# MorseCodeExternalMicCircuit_Eagle_schema.net
KiCad netlist of a schematic drawn in EAGLE
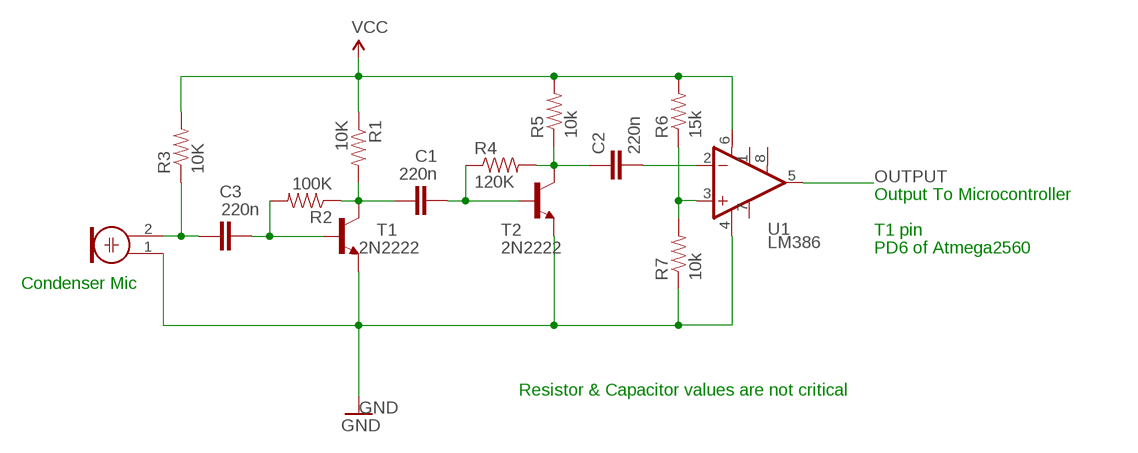
[diagram p0: schematic, sheet 1]

(export (version "E")
  (design (tool "Eeschema 10.0.6"))
  (components
    (comp (ref "C1")
      (value "220n")
      (footprint "eagle-import:CAP-PTH-SMALL-KIT")
      (libsource (lib "eagle-import") (part "0.1UF-50V-20%(PTH)KIT-EZ"))
    )
    (comp (ref "C2")
      (value "220n")
      (footprint "eagle-import:CAP-PTH-SMALL-KIT")
      (libsource (lib "eagle-import") (part "0.1UF-50V-20%(PTH)KIT-EZ"))
    )
    (comp (ref "C3")
      (value "220n")
      (footprint "eagle-import:CAP-PTH-SMALL-KIT")
      (libsource (lib "eagle-import") (part "0.1UF-50V-20%(PTH)KIT-EZ"))
    )
    (comp (ref "M1")
      (value "ELECTRET_MICROPHON-F6050AP")
      (footprint "eagle-import:F6050AP")
      (libsource (lib "eagle-import") (part "ELECTRET_MICROPHON-F6050AP"))
    )
    (comp (ref "R1")
      (value "10K")
      (footprint "eagle-import:AXIAL-0.3EZ")
      (libsource (lib "eagle-import") (part "RESISTOREZ"))
    )
    (comp (ref "R2")
      (value "100K")
      (footprint "eagle-import:AXIAL-0.3EZ")
      (libsource (lib "eagle-import") (part "RESISTOREZ"))
    )
    (comp (ref "R3")
      (value "10K")
      (footprint "eagle-import:AXIAL-0.3EZ")
      (libsource (lib "eagle-import") (part "RESISTOREZ"))
    )
    (comp (ref "R4")
      (value "120K")
      (footprint "eagle-import:AXIAL-0.3EZ")
      (libsource (lib "eagle-import") (part "RESISTOREZ"))
    )
    (comp (ref "R5")
      (value "10k")
      (footprint "eagle-import:AXIAL-0.3EZ")
      (libsource (lib "eagle-import") (part "RESISTOREZ"))
    )
    (comp (ref "R6")
      (value "15k")
      (footprint "eagle-import:AXIAL-0.3EZ")
      (libsource (lib "eagle-import") (part "RESISTOREZ"))
    )
    (comp (ref "R7")
      (value "10k")
      (footprint "eagle-import:AXIAL-0.3EZ")
      (libsource (lib "eagle-import") (part "RESISTOREZ"))
    )
    (comp (ref "T1")
      (value "2N2222")
      (footprint "eagle-import:TO18")
      (libsource (lib "eagle-import") (part "2N2222"))
    )
    (comp (ref "T2")
      (value "2N2222")
      (footprint "eagle-import:TO18")
      (libsource (lib "eagle-import") (part "2N2222"))
    )
    (comp (ref "U1")
      (value "LM386")
      (footprint "eagle-import:DIP08")
      (libsource (lib "eagle-import") (part "LM386"))
    )
  )
  (nets
    (net (code "1") (name "/OUTPUT") (class "Default")
      (node (ref "U1") (pin "5") (pinfunction "OUT_5") (pintype "output"))
    )
    (net (code "2") (name "GND") (class "Default")
      (node (ref "M1") (pin "1") (pinfunction "1_1") (pintype "passive"))
      (node (ref "R7") (pin "P$1") (pinfunction "1_P$1") (pintype "passive"))
      (node (ref "T1") (pin "1") (pinfunction "E_1") (pintype "passive"))
      (node (ref "T2") (pin "1") (pinfunction "E_1") (pintype "passive"))
      (node (ref "U1") (pin "4") (pinfunction "V-_4") (pintype "power_in"))
    )
    (net (code "3") (name "Net-(R1-2)") (class "Default")
      (node (ref "C1") (pin "1") (pinfunction "1_1") (pintype "passive"))
      (node (ref "R1") (pin "P$2") (pinfunction "2_P$2") (pintype "passive"))
      (node (ref "R2") (pin "P$1") (pinfunction "1_P$1") (pintype "passive"))
      (node (ref "T1") (pin "3") (pinfunction "C_3") (pintype "passive"))
    )
    (net (code "4") (name "Net-(R2-2)") (class "Default")
      (node (ref "C3") (pin "2") (pinfunction "2_2") (pintype "passive"))
      (node (ref "R2") (pin "P$2") (pinfunction "2_P$2") (pintype "passive"))
      (node (ref "T1") (pin "2") (pinfunction "B_2") (pintype "passive"))
    )
    (net (code "5") (name "Net-(R3-1)") (class "Default")
      (node (ref "C3") (pin "1") (pinfunction "1_1") (pintype "passive"))
      (node (ref "M1") (pin "2") (pinfunction "2_2") (pintype "passive"))
      (node (ref "R3") (pin "P$1") (pinfunction "1_P$1") (pintype "passive"))
    )
    (net (code "6") (name "Net-(R4-1)") (class "Default")
      (node (ref "C1") (pin "2") (pinfunction "2_2") (pintype "passive"))
      (node (ref "R4") (pin "P$1") (pinfunction "1_P$1") (pintype "passive"))
      (node (ref "T2") (pin "2") (pinfunction "B_2") (pintype "passive"))
    )
    (net (code "7") (name "Net-(R4-2)") (class "Default")
      (node (ref "C2") (pin "1") (pinfunction "1_1") (pintype "passive"))
      (node (ref "R4") (pin "P$2") (pinfunction "2_P$2") (pintype "passive"))
      (node (ref "R5") (pin "P$1") (pinfunction "1_P$1") (pintype "passive"))
      (node (ref "T2") (pin "3") (pinfunction "C_3") (pintype "passive"))
    )
    (net (code "8") (name "Net-(R6-1)") (class "Default")
      (node (ref "R6") (pin "P$1") (pinfunction "1_P$1") (pintype "passive"))
      (node (ref "R7") (pin "P$2") (pinfunction "2_P$2") (pintype "passive"))
      (node (ref "U1") (pin "3") (pinfunction "+IN_3") (pintype "input"))
    )
    (net (code "9") (name "Net-(U1--IN)") (class "Default")
      (node (ref "C2") (pin "2") (pinfunction "2_2") (pintype "passive"))
      (node (ref "U1") (pin "2") (pinfunction "-IN_2") (pintype "input"))
    )
    (net (code "10") (name "VCC") (class "Default")
      (node (ref "R1") (pin "P$1") (pinfunction "1_P$1") (pintype "passive"))
      (node (ref "R3") (pin "P$2") (pinfunction "2_P$2") (pintype "passive"))
      (node (ref "R5") (pin "P$2") (pinfunction "2_P$2") (pintype "passive"))
      (node (ref "R6") (pin "P$2") (pinfunction "2_P$2") (pintype "passive"))
      (node (ref "U1") (pin "6") (pinfunction "V+_6") (pintype "power_in"))
    )
    (net (code "11") (name "unconnected-(U1-BP-Pad7)") (class "Default")
      (node (ref "U1") (pin "7") (pinfunction "BP_7") (pintype "bidirectional"))
    )
    (net (code "12") (name "unconnected-(U1-GAIN-Pad1)") (class "Default")
      (node (ref "U1") (pin "1") (pinfunction "GAIN_1") (pintype "bidirectional"))
    )
    (net (code "13") (name "unconnected-(U1-GAIN-Pad8)") (class "Default")
      (node (ref "U1") (pin "8") (pinfunction "GAIN_8") (pintype "bidirectional"))
    )
  )
)
